# design.net
KiCad netlist of a schematic drawn in Altium Designer
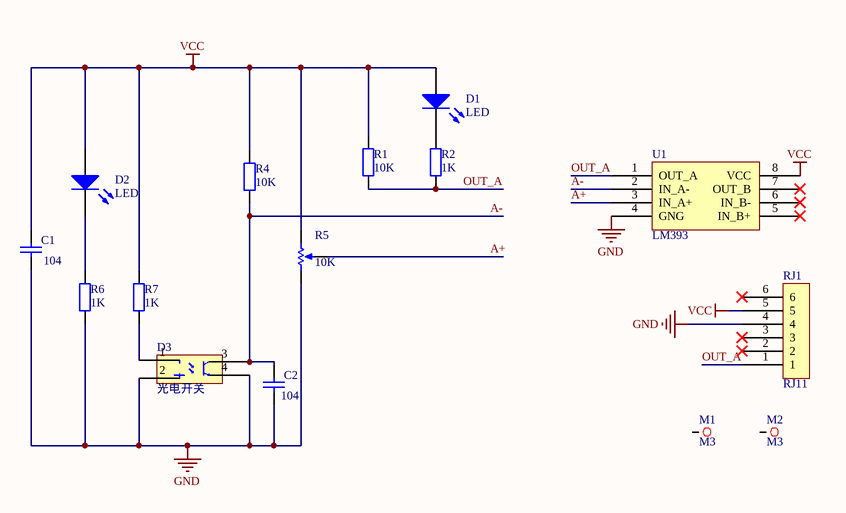
[diagram p0: 测速.SchDoc]

(export (version "E")
  (design (tool "Eeschema 10.0.6"))
  (components
    (comp (ref "C1")
      (value "104")
      (footprint "0603_C")
      (description "Capacitor")
      (fields (field (name "Comment") "Cap") (field (name "PUBLISHER") "Altium Limited"))
      (libsource (lib "Miscellaneous Devices") (part "Cap"))
    )
    (comp (ref "C2")
      (value "104")
      (footprint "0603_C")
      (description "Capacitor")
      (fields (field (name "Comment") "Cap") (field (name "PUBLISHER") "Altium Limited"))
      (libsource (lib "Miscellaneous Devices") (part "Cap"))
    )
    (comp (ref "D1")
      (value "LED")
      (footprint "0805")
      (description "Typical RED GaAs LED")
      (fields (field (name "PUBLISHER") "Altium Limited"))
      (libsource (lib "Miscellaneous Devices") (part "LED1"))
    )
    (comp (ref "D2")
      (value "LED")
      (footprint "0805")
      (description "Typical RED GaAs LED")
      (fields (field (name "PUBLISHER") "Altium Limited"))
      (libsource (lib "Miscellaneous Devices") (part "LED1"))
    )
    (comp (ref "D3") (value "光电开关") (footprint "光电开关") (libsource (lib "测速") (part "光电开关")))
    (comp (ref "M1") (value "M3") (footprint "M3") (libsource (lib "QQW-1.SCHLIB") (part "M3")))
    (comp (ref "M2") (value "M3") (footprint "M3") (libsource (lib "QQW-1.SCHLIB") (part "M3")))
    (comp (ref "R1")
      (value "10K")
      (footprint "0603_R")
      (description "Resistor")
      (fields (field (name "Comment") "Res2") (field (name "PUBLISHER") "Altium Limited"))
      (libsource (lib "Miscellaneous Devices") (part "Res2"))
    )
    (comp (ref "R2")
      (value "1K")
      (footprint "0603_R")
      (description "Resistor")
      (fields (field (name "Comment") "Res2") (field (name "PUBLISHER") "Altium Limited"))
      (libsource (lib "Miscellaneous Devices") (part "Res2"))
    )
    (comp (ref "R4")
      (value "10K")
      (footprint "0603_R")
      (description "Resistor")
      (fields (field (name "Comment") "Res2") (field (name "PUBLISHER") "Altium Limited"))
      (libsource (lib "Miscellaneous Devices") (part "Res2"))
    )
    (comp (ref "R5")
      (value "10K")
      (footprint "电位器")
      (description "Potentiometer")
      (fields (field (name "Comment") "RPot") (field (name "PUBLISHER") "Altium Limited"))
      (libsource (lib "Miscellaneous Devices") (part "RPot"))
    )
    (comp (ref "R6")
      (value "1K")
      (footprint "0603_R")
      (description "Resistor")
      (fields (field (name "Comment") "Res2") (field (name "PUBLISHER") "Altium Limited"))
      (libsource (lib "Miscellaneous Devices") (part "Res2"))
    )
    (comp (ref "R7")
      (value "1K")
      (footprint "0603_R")
      (description "Resistor")
      (fields (field (name "Comment") "Res2") (field (name "PUBLISHER") "Altium Limited"))
      (libsource (lib "Miscellaneous Devices") (part "Res2"))
    )
    (comp (ref "RJ1") (value "RJ11") (footprint "RJ11") (libsource (lib "VBT6") (part "RJ11")))
    (comp (ref "U1") (value "LM393") (footprint "SO-8") (libsource (lib "Infrared") (part "LM393")))
  )
  (nets
    (net (code "1") (name "/A+") (class "Default")
      (node (ref "R5") (pin "3") (pinfunction "TAP_3") (pintype "passive"))
      (node (ref "U1") (pin "3") (pinfunction "IN_A+_3") (pintype "passive"))
    )
    (net (code "2") (name "/A-") (class "Default")
      (node (ref "C2") (pin "2") (pinfunction "2_2") (pintype "passive"))
      (node (ref "D3") (pin "3") (pinfunction "3_3") (pintype "passive"))
      (node (ref "R4") (pin "1") (pinfunction "1_1") (pintype "passive"))
      (node (ref "U1") (pin "2") (pinfunction "IN_A-_2") (pintype "passive"))
    )
    (net (code "3") (name "/OUT_A") (class "Default")
      (node (ref "R1") (pin "1") (pinfunction "1_1") (pintype "passive"))
      (node (ref "R2") (pin "1") (pinfunction "1_1") (pintype "passive"))
      (node (ref "RJ1") (pin "1") (pinfunction "1_1") (pintype "passive"))
      (node (ref "U1") (pin "1") (pinfunction "OUT_A_1") (pintype "passive"))
    )
    (net (code "4") (name "GND") (class "Default")
      (node (ref "C1") (pin "1") (pinfunction "1_1") (pintype "passive"))
      (node (ref "C2") (pin "1") (pinfunction "1_1") (pintype "passive"))
      (node (ref "D3") (pin "2") (pinfunction "2_2") (pintype "passive"))
      (node (ref "D3") (pin "4") (pinfunction "4_4") (pintype "passive"))
      (node (ref "R5") (pin "1") (pinfunction "TOP_1") (pintype "passive"))
      (node (ref "R6") (pin "1") (pinfunction "1_1") (pintype "passive"))
      (node (ref "RJ1") (pin "4") (pinfunction "4_4") (pintype "passive"))
      (node (ref "U1") (pin "4") (pinfunction "GNG_4") (pintype "passive"))
    )
    (net (code "5") (name "Net-(D1-K)") (class "Default")
      (node (ref "D1") (pin "2") (pinfunction "K_2") (pintype "passive"))
      (node (ref "R2") (pin "2") (pinfunction "2_2") (pintype "passive"))
    )
    (net (code "6") (name "Net-(D2-K)") (class "Default")
      (node (ref "D2") (pin "2") (pinfunction "K_2") (pintype "passive"))
      (node (ref "R6") (pin "2") (pinfunction "2_2") (pintype "passive"))
    )
    (net (code "7") (name "Net-(D3-Pad1)") (class "Default")
      (node (ref "D3") (pin "1") (pinfunction "1_1") (pintype "passive"))
      (node (ref "R7") (pin "1") (pinfunction "1_1") (pintype "passive"))
    )
    (net (code "8") (name "VCC") (class "Default")
      (node (ref "C1") (pin "2") (pinfunction "2_2") (pintype "passive"))
      (node (ref "D1") (pin "1") (pinfunction "A_1") (pintype "passive"))
      (node (ref "D2") (pin "1") (pinfunction "A_1") (pintype "passive"))
      (node (ref "R1") (pin "2") (pinfunction "2_2") (pintype "passive"))
      (node (ref "R4") (pin "2") (pinfunction "2_2") (pintype "passive"))
      (node (ref "R5") (pin "2") (pinfunction "BOT_2") (pintype "passive"))
      (node (ref "R7") (pin "2") (pinfunction "2_2") (pintype "passive"))
      (node (ref "RJ1") (pin "5") (pinfunction "5_5") (pintype "passive"))
      (node (ref "U1") (pin "8") (pinfunction "VCC_8") (pintype "passive"))
    )
    (net (code "9") (name "unconnected-(M1-Pad0)") (class "Default")
      (node (ref "M1") (pin "0") (pinfunction "0_0") (pintype "passive"))
    )
    (net (code "10") (name "unconnected-(M2-Pad0)") (class "Default")
      (node (ref "M2") (pin "0") (pinfunction "0_0") (pintype "passive"))
    )
    (net (code "11") (name "unconnected-(RJ1-Pad2)") (class "Default")
      (node (ref "RJ1") (pin "2") (pinfunction "2_2") (pintype "passive+no_connect"))
    )
    (net (code "12") (name "unconnected-(RJ1-Pad3)") (class "Default")
      (node (ref "RJ1") (pin "3") (pinfunction "3_3") (pintype "passive+no_connect"))
    )
    (net (code "13") (name "unconnected-(RJ1-Pad6)") (class "Default")
      (node (ref "RJ1") (pin "6") (pinfunction "6_6") (pintype "passive+no_connect"))
    )
    (net (code "14") (name "unconnected-(U1-IN_B+-Pad5)") (class "Default")
      (node (ref "U1") (pin "5") (pinfunction "IN_B+_5") (pintype "passive+no_connect"))
    )
    (net (code "15") (name "unconnected-(U1-IN_B--Pad6)") (class "Default")
      (node (ref "U1") (pin "6") (pinfunction "IN_B-_6") (pintype "passive+no_connect"))
    )
    (net (code "16") (name "unconnected-(U1-OUT_B-Pad7)") (class "Default")
      (node (ref "U1") (pin "7") (pinfunction "OUT_B_7") (pintype "passive+no_connect"))
    )
  )
)
